# ETH_CON.net
KiCad netlist of a schematic drawn in Altium Designer
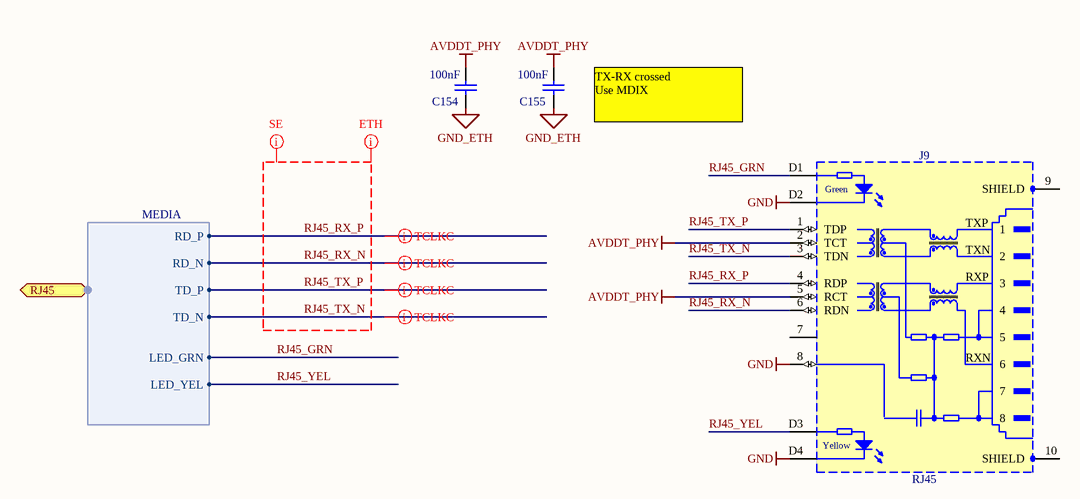
[diagram p0: ETH_CON.SchDoc]

(export (version "E")
  (design (tool "Eeschema 10.0.6"))
  (components
    (comp (ref "C154")
      (value "100nF")
      (footprint "CAPC0603X33N")
      (description "Non-polarised capacitor")
      (fields
        (field (name "PART NUMBER") "CC0201_100NF_6.3V_10%_X5R")
        (field (name "VOLTAGE") "6.3V")
        (field (name "AUTHOR") "CERN DEM JLC")
      )
      (libsource (lib "Capacitors") (part "Capacitor - non polarized"))
    )
    (comp (ref "C155")
      (value "100nF")
      (footprint "CAPC0603X33N")
      (description "Non-polarised capacitor")
      (fields
        (field (name "PART NUMBER") "CC0201_100NF_6.3V_10%_X5R")
        (field (name "VOLTAGE") "6.3V")
        (field (name "AUTHOR") "CERN DEM JLC")
      )
      (libsource (lib "Capacitors") (part "Capacitor - non polarized"))
    )
    (comp (ref "J9")
      (value "RJ45")
      (footprint "TYCO_5-6605308-1")
      (fields
        (field (name "PART NUMBER") "TYCO_5-6605308-1")
        (field (name "MANUFACTURER") "TYCO ELECTRONICS")
        (field (name "MANUFACTURER PART NUMBER") "5-6605308-1")
        (field (name "AUTHOR") "CERN DEM JLC")
      )
      (libsource (lib "Connectors") (part "TYCO_5-6605308-1"))
    )
  )
  (nets
    (net (code "2") (name "/RJ45_GRN") (class "Default")
      (node (ref "J9") (pin "D1") (pinfunction "D1_D1") (pintype "passive"))
    )
    (net (code "3") (name "/RJ45_RX_N") (class "Default")
      (node (ref "J9") (pin "6") (pinfunction "RDN_6") (pintype "bidirectional"))
    )
    (net (code "4") (name "/RJ45_RX_P") (class "Default")
      (node (ref "J9") (pin "4") (pinfunction "RDP_4") (pintype "bidirectional"))
    )
    (net (code "5") (name "/RJ45_TX_N") (class "Default")
      (node (ref "J9") (pin "3") (pinfunction "TDN_3") (pintype "bidirectional"))
    )
    (net (code "6") (name "/RJ45_TX_P") (class "Default")
      (node (ref "J9") (pin "1") (pinfunction "TDP_1") (pintype "bidirectional"))
    )
    (net (code "7") (name "/RJ45_YEL") (class "Default")
      (node (ref "J9") (pin "D3") (pinfunction "D3_D3") (pintype "passive"))
    )
    (net (code "9") (name "AVDDT_PHY") (class "Default")
      (node (ref "C154") (pin "2") (pinfunction "2_2") (pintype "passive"))
      (node (ref "C155") (pin "2") (pinfunction "2_2") (pintype "passive"))
      (node (ref "J9") (pin "2") (pinfunction "TCT_2") (pintype "bidirectional"))
      (node (ref "J9") (pin "5") (pinfunction "RCT_5") (pintype "bidirectional"))
    )
    (net (code "10") (name "GND") (class "Default")
      (node (ref "J9") (pin "8") (pinfunction "8_8") (pintype "bidirectional"))
      (node (ref "J9") (pin "D2") (pinfunction "D2_D2") (pintype "passive"))
      (node (ref "J9") (pin "D4") (pinfunction "D4_D4") (pintype "passive"))
    )
    (net (code "11") (name "GND_ETH") (class "Default")
      (node (ref "C154") (pin "1") (pinfunction "1_1") (pintype "passive"))
      (node (ref "C155") (pin "1") (pinfunction "1_1") (pintype "passive"))
    )
    (net (code "12") (name "unconnected-(J9-Pad7)") (class "Default")
      (node (ref "J9") (pin "7") (pinfunction "7_7") (pintype "passive"))
    )
    (net (code "13") (name "unconnected-(J9-SHIELD-Pad9)") (class "Default")
      (node (ref "J9") (pin "9") (pinfunction "SHIELD_9") (pintype "power_in"))
    )
    (net (code "14") (name "unconnected-(J9-SHIELD-Pad10)") (class "Default")
      (node (ref "J9") (pin "10") (pinfunction "SHIELD_10") (pintype "power_in"))
    )
  )
)
